# MIXED_FILTER.net
KiCad netlist of a schematic drawn in Altium Designer
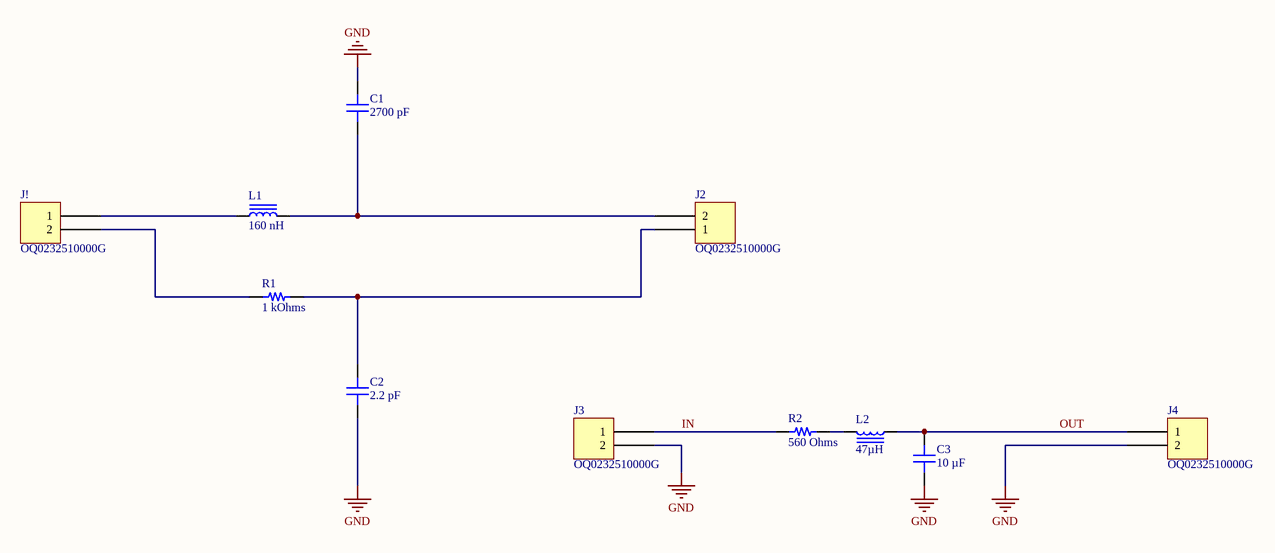
[diagram p0: MIXED_FILTER.SchDoc]

(export (version "E")
  (design (tool "Eeschema 10.0.6"))
  (components
    (comp (ref "C1")
      (value "2700 pF")
      (footprint "CAP 0603_1608")
      (description "CAP CER 2700PF 25V NP0 0603")
      (fields (field (name "PART NUMBER") "C0603C272F3GAC7867") (field (name "MANUFACTURER") "KEMET"))
      (libsource (lib "Celestial Altium Library - altium_library") (part "Capacitor"))
    )
    (comp (ref "C2")
      (value "2.2 pF")
      (footprint "CAP 0603_1608")
      (description "CAP CER 2.2PF 250V C0G/NP0 0603")
      (fields
        (field (name "PART NUMBER") "600S2R2AT250XT")
        (field (name "MANUFACTURER") "American Technical Ceramics")
      )
      (libsource (lib "Celestial Altium Library - altium_library") (part "Capacitor"))
    )
    (comp (ref "C3")
      (value "10 µF")
      (footprint "CAP 0603_1608")
      (description "CAP CER 10UF 10V X5R 0603")
      (fields
        (field (name "PART NUMBER") "MD0603BW106M100NHT-EM")
        (field (name "MANUFACTURER") "Knowles Novacap")
      )
      (libsource (lib "Celestial Altium Library - altium_library") (part "Capacitor"))
    )
    (comp (ref "J!")
      (value "OQ0232510000G")
      (footprint "FCI 06-381-2PIN")
      (description "TERM BLOCK HDR 2POS 90DEG 3.81MM")
      (fields (field (name "MANUFACTURER") "Amphenol Anytek"))
      (libsource (lib "") (part "2 Pin_2"))
    )
    (comp (ref "J2")
      (value "OQ0232510000G")
      (footprint "FCI 06-381-2PIN")
      (description "TERM BLOCK HDR 2POS 90DEG 3.81MM")
      (fields (field (name "MANUFACTURER") "Amphenol Anytek"))
      (libsource (lib "Celestial Altium Library - altium_library") (part "2 Pin"))
    )
    (comp (ref "J3")
      (value "OQ0232510000G")
      (footprint "FCI 06-381-2PIN")
      (description "TERM BLOCK HDR 2POS 90DEG 3.81MM")
      (fields (field (name "MANUFACTURER") "Amphenol Anytek"))
      (libsource (lib "") (part "2 Pin_2"))
    )
    (comp (ref "J4")
      (value "OQ0232510000G")
      (footprint "FCI 06-381-2PIN")
      (description "TERM BLOCK HDR 2POS 90DEG 3.81MM")
      (fields (field (name "MANUFACTURER") "Amphenol Anytek"))
      (libsource (lib "") (part "2 Pin_1"))
    )
    (comp (ref "L1")
      (value "160 nH")
      (footprint "IND 0402_1005 RF WW")
      (description "FIXED IND 160NH 480MA 330MOHM SM")
      (fields
        (field (name "PART NUMBER") "LQW15CNR16J00D")
        (field (name "MANUFACTURER") "Murata Electronics")
      )
      (libsource (lib "Celestial Altium Library - altium_library") (part "Inductor"))
    )
    (comp (ref "L2")
      (value "47µH")
      (footprint "IND 0603_1608 RF WW")
      (description "INDUCTORPOWER LINE 0603 47H 20%")
      (fields (field (name "PART NUMBER") "L0603B470MPWFT") (field (name "MANUFACTURER") "KEMET"))
      (libsource (lib "Celestial Altium Library - altium_library") (part "Inductor"))
    )
    (comp (ref "R1")
      (value "1 kOhms")
      (footprint "RES 0603_1608")
      (description "RES SMD 1K OHM 0.1% 1/16W 0603")
      (fields
        (field (name "PART NUMBER") "CPF0603B1K0E")
        (field (name "MANUFACTURER") "TE Connectivity Passive Product")
      )
      (libsource (lib "Celestial Altium Library - altium_library") (part "Resistor"))
    )
    (comp (ref "R2")
      (value "560 Ohms")
      (footprint "RES 0603_1608")
      (description "RES 560 OHM 1% 1/4W 0603")
      (fields
        (field (name "PART NUMBER") "CRGP0603F560R")
        (field (name "MANUFACTURER") "TE Connectivity Passive Product")
      )
      (libsource (lib "Celestial Altium Library - altium_library") (part "Resistor"))
    )
  )
  (nets
    (net (code "1") (name "/IN") (class "Default")
      (node (ref "J3") (pin "1") (pinfunction "1_1") (pintype "passive"))
      (node (ref "R2") (pin "1") (pinfunction "1_1") (pintype "passive"))
    )
    (net (code "2") (name "/OUT") (class "Default")
      (node (ref "C3") (pin "2") (pinfunction "2_2") (pintype "passive"))
      (node (ref "J4") (pin "1") (pinfunction "1_1") (pintype "passive"))
      (node (ref "L2") (pin "1") (pinfunction "1_1") (pintype "passive"))
    )
    (net (code "3") (name "GND") (class "Default")
      (node (ref "C1") (pin "2") (pinfunction "2_2") (pintype "passive"))
      (node (ref "C2") (pin "2") (pinfunction "2_2") (pintype "passive"))
      (node (ref "C3") (pin "1") (pinfunction "1_1") (pintype "passive"))
      (node (ref "J3") (pin "2") (pinfunction "2_2") (pintype "passive"))
      (node (ref "J4") (pin "2") (pinfunction "2_2") (pintype "passive"))
    )
    (net (code "4") (name "Net-(C1-Pad1)") (class "Default")
      (node (ref "C1") (pin "1") (pinfunction "1_1") (pintype "passive"))
      (node (ref "J2") (pin "2") (pinfunction "2_2") (pintype "passive"))
      (node (ref "L1") (pin "2") (pinfunction "2_2") (pintype "passive"))
    )
    (net (code "5") (name "Net-(C2-Pad1)") (class "Default")
      (node (ref "C2") (pin "1") (pinfunction "1_1") (pintype "passive"))
      (node (ref "J2") (pin "1") (pinfunction "1_1") (pintype "passive"))
      (node (ref "R1") (pin "2") (pinfunction "2_2") (pintype "passive"))
    )
    (net (code "6") (name "Net-(J!-Pad1)") (class "Default")
      (node (ref "J!") (pin "1") (pinfunction "1_1") (pintype "passive"))
      (node (ref "L1") (pin "1") (pinfunction "1_1") (pintype "passive"))
    )
    (net (code "7") (name "Net-(J!-Pad2)") (class "Default")
      (node (ref "J!") (pin "2") (pinfunction "2_2") (pintype "passive"))
      (node (ref "R1") (pin "1") (pinfunction "1_1") (pintype "passive"))
    )
    (net (code "8") (name "Net-(L2-Pad2)") (class "Default")
      (node (ref "L2") (pin "2") (pinfunction "2_2") (pintype "passive"))
      (node (ref "R2") (pin "2") (pinfunction "2_2") (pintype "passive"))
    )
  )
)
